# touch4.net
KiCad netlist of a schematic drawn in EAGLE
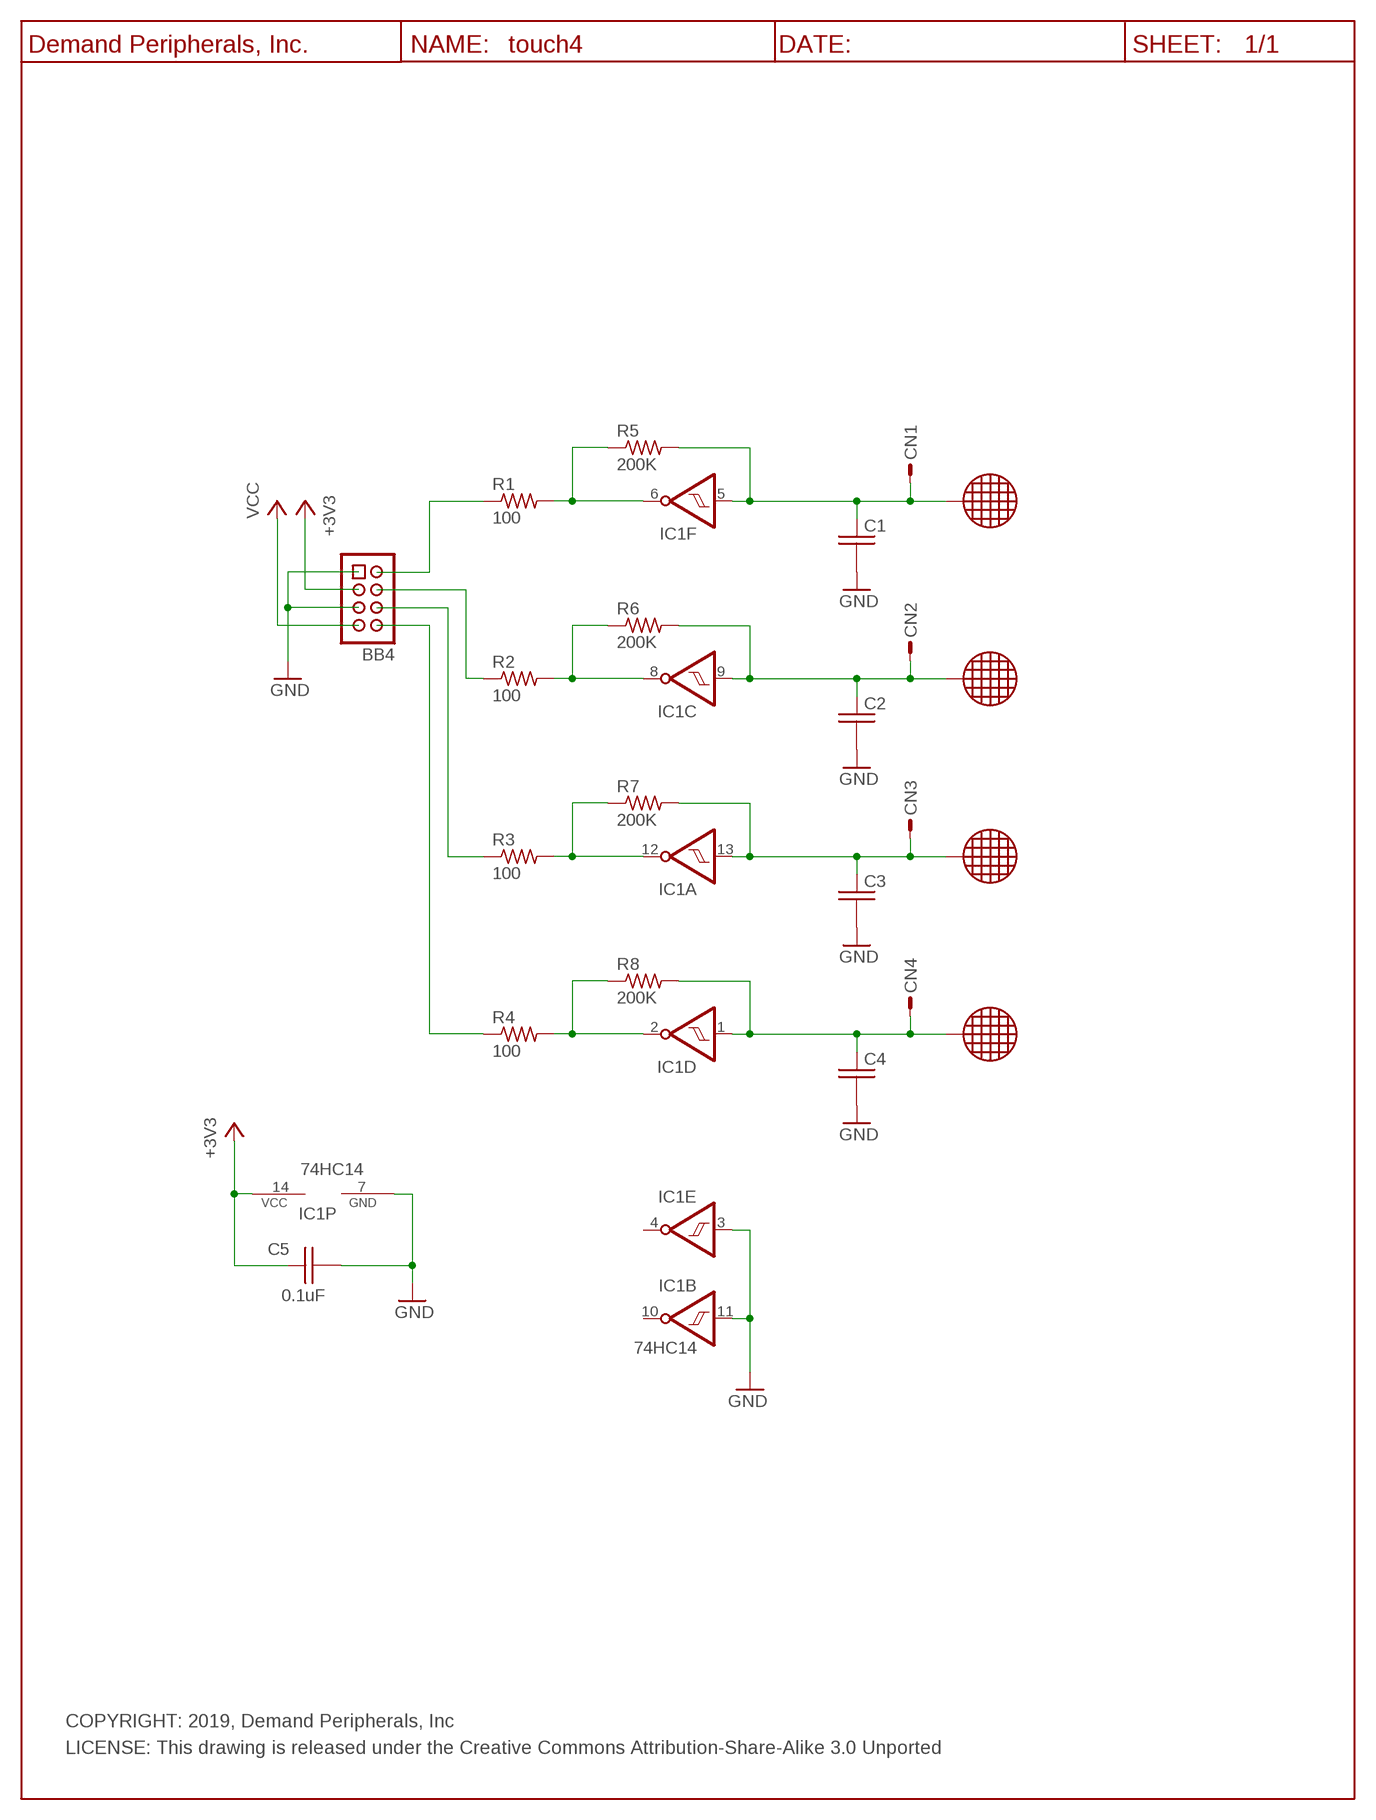
[diagram p0: schematic, sheet 1]

(export (version "E")
  (design (tool "Eeschema 10.0.6"))
  (components
    (comp (ref "BB4")
      (value "BB_CON")
      (footprint "eagle-import:HDR-4X2")
      (libsource (lib "eagle-import") (part "HDR-4X2-SHR"))
    )
    (comp (ref "C1")
      (value "C33PF_C0603")
      (footprint "eagle-import:C0603")
      (libsource (lib "eagle-import") (part "C33PF_C0603"))
    )
    (comp (ref "C2")
      (value "C33PF_C0603")
      (footprint "eagle-import:C0603")
      (libsource (lib "eagle-import") (part "C33PF_C0603"))
    )
    (comp (ref "C3")
      (value "C33PF_C0603")
      (footprint "eagle-import:C0603")
      (libsource (lib "eagle-import") (part "C33PF_C0603"))
    )
    (comp (ref "C4")
      (value "C33PF_C0603")
      (footprint "eagle-import:C0603")
      (libsource (lib "eagle-import") (part "C33PF_C0603"))
    )
    (comp (ref "C5")
      (value "0.1uF")
      (footprint "eagle-import:C0603")
      (libsource (lib "eagle-import") (part "C0.1UF_C0603"))
    )
    (comp (ref "CN1")
      (value "PAD1")
      (footprint "eagle-import:PAD1")
      (libsource (lib "eagle-import") (part "PAD1"))
    )
    (comp (ref "CN2")
      (value "PAD1")
      (footprint "eagle-import:PAD1")
      (libsource (lib "eagle-import") (part "PAD1"))
    )
    (comp (ref "CN3")
      (value "PAD1")
      (footprint "eagle-import:PAD1")
      (libsource (lib "eagle-import") (part "PAD1"))
    )
    (comp (ref "CN4")
      (value "PAD1")
      (footprint "eagle-import:PAD1")
      (libsource (lib "eagle-import") (part "PAD1"))
    )
    (comp (ref "IC1")
      (value "74HC14")
      (footprint "eagle-import:SO14")
      (libsource (lib "eagle-import") (part "7414"))
    )
    (comp (ref "R1")
      (value "100")
      (footprint "eagle-import:R0603")
      (libsource (lib "eagle-import") (part "R100_R0603"))
    )
    (comp (ref "R2")
      (value "100")
      (footprint "eagle-import:R0603")
      (libsource (lib "eagle-import") (part "R100_R0603"))
    )
    (comp (ref "R3")
      (value "100")
      (footprint "eagle-import:R0603")
      (libsource (lib "eagle-import") (part "R100_R0603"))
    )
    (comp (ref "R4")
      (value "100")
      (footprint "eagle-import:R0603")
      (libsource (lib "eagle-import") (part "R100_R0603"))
    )
    (comp (ref "R5")
      (value "200K")
      (footprint "eagle-import:R0603")
      (libsource (lib "eagle-import") (part "R200K_R0603"))
    )
    (comp (ref "R6")
      (value "200K")
      (footprint "eagle-import:R0603")
      (libsource (lib "eagle-import") (part "R200K_R0603"))
    )
    (comp (ref "R7")
      (value "200K")
      (footprint "eagle-import:R0603")
      (libsource (lib "eagle-import") (part "R200K_R0603"))
    )
    (comp (ref "R8")
      (value "200K")
      (footprint "eagle-import:R0603")
      (libsource (lib "eagle-import") (part "R200K_R0603"))
    )
    (comp (ref "U$1")
      (value "DP_FRAME_P")
      (footprint "eagle-import:P_FRAME")
      (libsource (lib "eagle-import") (part "DP_FRAME_P"))
    )
    (comp (ref "U$5")
      (value "TOUCH-9MM")
      (footprint "eagle-import:TOUCH-9MM")
      (libsource (lib "eagle-import") (part "TOUCH-9MM"))
    )
    (comp (ref "U$6")
      (value "TOUCH-9MM")
      (footprint "eagle-import:TOUCH-9MM")
      (libsource (lib "eagle-import") (part "TOUCH-9MM"))
    )
    (comp (ref "U$7")
      (value "TOUCH-9MM")
      (footprint "eagle-import:TOUCH-9MM")
      (libsource (lib "eagle-import") (part "TOUCH-9MM"))
    )
    (comp (ref "U$9")
      (value "TOUCH-9MM")
      (footprint "eagle-import:TOUCH-9MM")
      (libsource (lib "eagle-import") (part "TOUCH-9MM"))
    )
  )
  (nets
    (net (code "1") (name "+3V3") (class "Default")
      (node (ref "BB4") (pin "3") (pinfunction "3_3") (pintype "passive"))
      (node (ref "C5") (pin "1") (pinfunction "1_1") (pintype "passive"))
      (node (ref "IC1") (pin "14") (pinfunction "VCC_14") (pintype "power_in"))
    )
    (net (code "2") (name "GND") (class "Default")
      (node (ref "BB4") (pin "1") (pinfunction "1_1") (pintype "passive"))
      (node (ref "BB4") (pin "5") (pinfunction "5_5") (pintype "passive"))
      (node (ref "C1") (pin "2") (pinfunction "2_2") (pintype "passive"))
      (node (ref "C2") (pin "2") (pinfunction "2_2") (pintype "passive"))
      (node (ref "C3") (pin "2") (pinfunction "2_2") (pintype "passive"))
      (node (ref "C4") (pin "2") (pinfunction "2_2") (pintype "passive"))
      (node (ref "C5") (pin "2") (pinfunction "2_2") (pintype "passive"))
      (node (ref "IC1") (pin "11") (pinfunction "I_11") (pintype "input"))
      (node (ref "IC1") (pin "3") (pinfunction "I_3") (pintype "input"))
      (node (ref "IC1") (pin "7") (pinfunction "GND_7") (pintype "power_in"))
    )
    (net (code "3") (name "Net-(BB4-Pad2)") (class "Default")
      (node (ref "BB4") (pin "2") (pinfunction "2_2") (pintype "passive"))
      (node (ref "R1") (pin "1") (pinfunction "1_1") (pintype "passive"))
    )
    (net (code "4") (name "Net-(BB4-Pad4)") (class "Default")
      (node (ref "BB4") (pin "4") (pinfunction "4_4") (pintype "passive"))
      (node (ref "R2") (pin "1") (pinfunction "1_1") (pintype "passive"))
    )
    (net (code "5") (name "Net-(BB4-Pad6)") (class "Default")
      (node (ref "BB4") (pin "6") (pinfunction "6_6") (pintype "passive"))
      (node (ref "R3") (pin "1") (pinfunction "1_1") (pintype "passive"))
    )
    (net (code "6") (name "Net-(BB4-Pad8)") (class "Default")
      (node (ref "BB4") (pin "8") (pinfunction "8_8") (pintype "passive"))
      (node (ref "R4") (pin "1") (pinfunction "1_1") (pintype "passive"))
    )
    (net (code "7") (name "Net-(IC1A-I)") (class "Default")
      (node (ref "C3") (pin "1") (pinfunction "1_1") (pintype "passive"))
      (node (ref "CN3") (pin "1") (pinfunction "1_1") (pintype "passive"))
      (node (ref "IC1") (pin "13") (pinfunction "I_13") (pintype "input"))
      (node (ref "R7") (pin "2") (pinfunction "2_2") (pintype "passive"))
      (node (ref "U$7") (pin "1") (pinfunction "P$1_1") (pintype "passive"))
    )
    (net (code "8") (name "Net-(IC1A-O)") (class "Default")
      (node (ref "IC1") (pin "12") (pinfunction "O_12") (pintype "output"))
      (node (ref "R3") (pin "2") (pinfunction "2_2") (pintype "passive"))
      (node (ref "R7") (pin "1") (pinfunction "1_1") (pintype "passive"))
    )
    (net (code "9") (name "Net-(IC1C-I)") (class "Default")
      (node (ref "C2") (pin "1") (pinfunction "1_1") (pintype "passive"))
      (node (ref "CN2") (pin "1") (pinfunction "1_1") (pintype "passive"))
      (node (ref "IC1") (pin "9") (pinfunction "I_9") (pintype "input"))
      (node (ref "R6") (pin "2") (pinfunction "2_2") (pintype "passive"))
      (node (ref "U$6") (pin "1") (pinfunction "P$1_1") (pintype "passive"))
    )
    (net (code "10") (name "Net-(IC1C-O)") (class "Default")
      (node (ref "IC1") (pin "8") (pinfunction "O_8") (pintype "output"))
      (node (ref "R2") (pin "2") (pinfunction "2_2") (pintype "passive"))
      (node (ref "R6") (pin "1") (pinfunction "1_1") (pintype "passive"))
    )
    (net (code "11") (name "Net-(IC1D-I)") (class "Default")
      (node (ref "C4") (pin "1") (pinfunction "1_1") (pintype "passive"))
      (node (ref "CN4") (pin "1") (pinfunction "1_1") (pintype "passive"))
      (node (ref "IC1") (pin "1") (pinfunction "I_1") (pintype "input"))
      (node (ref "R8") (pin "2") (pinfunction "2_2") (pintype "passive"))
      (node (ref "U$9") (pin "1") (pinfunction "P$1_1") (pintype "passive"))
    )
    (net (code "12") (name "Net-(IC1D-O)") (class "Default")
      (node (ref "IC1") (pin "2") (pinfunction "O_2") (pintype "output"))
      (node (ref "R4") (pin "2") (pinfunction "2_2") (pintype "passive"))
      (node (ref "R8") (pin "1") (pinfunction "1_1") (pintype "passive"))
    )
    (net (code "13") (name "Net-(IC1F-I)") (class "Default")
      (node (ref "C1") (pin "1") (pinfunction "1_1") (pintype "passive"))
      (node (ref "CN1") (pin "1") (pinfunction "1_1") (pintype "passive"))
      (node (ref "IC1") (pin "5") (pinfunction "I_5") (pintype "input"))
      (node (ref "R5") (pin "2") (pinfunction "2_2") (pintype "passive"))
      (node (ref "U$5") (pin "1") (pinfunction "P$1_1") (pintype "passive"))
    )
    (net (code "14") (name "Net-(IC1F-O)") (class "Default")
      (node (ref "IC1") (pin "6") (pinfunction "O_6") (pintype "output"))
      (node (ref "R1") (pin "2") (pinfunction "2_2") (pintype "passive"))
      (node (ref "R5") (pin "1") (pinfunction "1_1") (pintype "passive"))
    )
    (net (code "15") (name "VCC") (class "Default")
      (node (ref "BB4") (pin "7") (pinfunction "7_7") (pintype "passive"))
    )
    (net (code "16") (name "unconnected-(IC1B-O-Pad10)") (class "Default")
      (node (ref "IC1") (pin "10") (pinfunction "O_10") (pintype "output"))
    )
    (net (code "17") (name "unconnected-(IC1E-O-Pad4)") (class "Default")
      (node (ref "IC1") (pin "4") (pinfunction "O_4") (pintype "output"))
    )
  )
)
